# Ports.net
KiCad netlist of a schematic drawn in Altium Designer
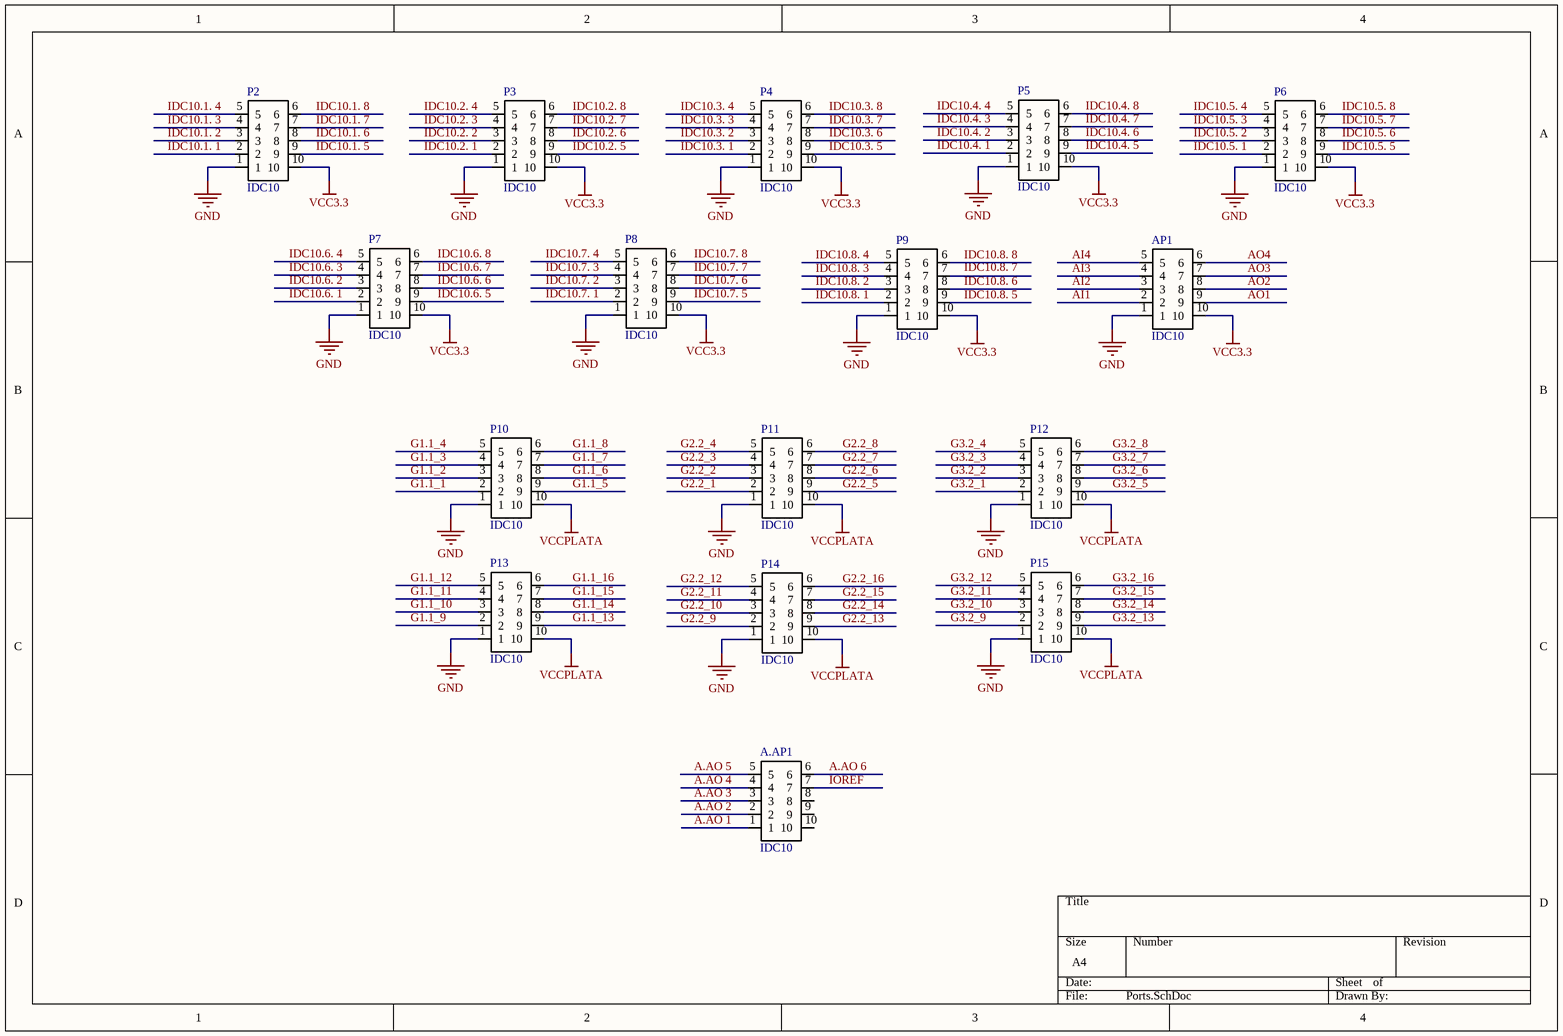
[diagram p0: Ports.SchDoc]

(export (version "E")
  (design (tool "Eeschema 10.0.6"))
  (components
    (comp (ref "A.AP1")
      (value "IDC10")
      (footprint "PcbLib1:IDC10")
      (libsource (lib "Library") (part "IDC10"))
    )
    (comp (ref "AP1") (value "IDC10") (footprint "PcbLib1:IDC10") (libsource (lib "Library") (part "IDC10")))
    (comp (ref "P2") (value "IDC10") (footprint "PcbLib1:IDC10") (libsource (lib "Library") (part "IDC10")))
    (comp (ref "P3") (value "IDC10") (footprint "PcbLib1:IDC10") (libsource (lib "Library") (part "IDC10")))
    (comp (ref "P4") (value "IDC10") (footprint "PcbLib1:IDC10") (libsource (lib "Library") (part "IDC10")))
    (comp (ref "P5") (value "IDC10") (footprint "PcbLib1:IDC10") (libsource (lib "Library") (part "IDC10")))
    (comp (ref "P6") (value "IDC10") (footprint "PcbLib1:IDC10") (libsource (lib "Library") (part "IDC10")))
    (comp (ref "P7") (value "IDC10") (footprint "PcbLib1:IDC10") (libsource (lib "Library") (part "IDC10")))
    (comp (ref "P8") (value "IDC10") (footprint "PcbLib1:IDC10") (libsource (lib "Library") (part "IDC10")))
    (comp (ref "P9") (value "IDC10") (footprint "PcbLib1:IDC10") (libsource (lib "Library") (part "IDC10")))
    (comp (ref "P10") (value "IDC10") (footprint "PcbLib1:IDC10") (libsource (lib "Library") (part "IDC10")))
    (comp (ref "P11") (value "IDC10") (footprint "PcbLib1:IDC10") (libsource (lib "Library") (part "IDC10")))
    (comp (ref "P12") (value "IDC10") (footprint "PcbLib1:IDC10") (libsource (lib "Library") (part "IDC10")))
    (comp (ref "P13") (value "IDC10") (footprint "PcbLib1:IDC10") (libsource (lib "Library") (part "IDC10")))
    (comp (ref "P14") (value "IDC10") (footprint "PcbLib1:IDC10") (libsource (lib "Library") (part "IDC10")))
    (comp (ref "P15") (value "IDC10") (footprint "PcbLib1:IDC10") (libsource (lib "Library") (part "IDC10")))
  )
  (nets
    (net (code "1") (name "/A.AO 1") (class "Default")
      (node (ref "A.AP1") (pin "1") (pinfunction "1_1") (pintype "passive"))
    )
    (net (code "2") (name "/A.AO 2") (class "Default")
      (node (ref "A.AP1") (pin "2") (pinfunction "2_2") (pintype "passive"))
    )
    (net (code "3") (name "/A.AO 3") (class "Default")
      (node (ref "A.AP1") (pin "3") (pinfunction "3_3") (pintype "passive"))
    )
    (net (code "4") (name "/A.AO 4") (class "Default")
      (node (ref "A.AP1") (pin "4") (pinfunction "4_4") (pintype "passive"))
    )
    (net (code "5") (name "/A.AO 5") (class "Default")
      (node (ref "A.AP1") (pin "5") (pinfunction "5_5") (pintype "passive"))
    )
    (net (code "6") (name "/A.AO 6") (class "Default")
      (node (ref "A.AP1") (pin "6") (pinfunction "6_6") (pintype "passive"))
    )
    (net (code "7") (name "/AI1") (class "Default")
      (node (ref "AP1") (pin "2") (pinfunction "2_2") (pintype "passive"))
    )
    (net (code "8") (name "/AI2") (class "Default")
      (node (ref "AP1") (pin "3") (pinfunction "3_3") (pintype "passive"))
    )
    (net (code "9") (name "/AI3") (class "Default")
      (node (ref "AP1") (pin "4") (pinfunction "4_4") (pintype "passive"))
    )
    (net (code "10") (name "/AI4") (class "Default")
      (node (ref "AP1") (pin "5") (pinfunction "5_5") (pintype "passive"))
    )
    (net (code "11") (name "/AO1") (class "Default")
      (node (ref "AP1") (pin "9") (pinfunction "9_9") (pintype "passive"))
    )
    (net (code "12") (name "/AO2") (class "Default")
      (node (ref "AP1") (pin "8") (pinfunction "8_8") (pintype "passive"))
    )
    (net (code "13") (name "/AO3") (class "Default")
      (node (ref "AP1") (pin "7") (pinfunction "7_7") (pintype "passive"))
    )
    (net (code "14") (name "/AO4") (class "Default")
      (node (ref "AP1") (pin "6") (pinfunction "6_6") (pintype "passive"))
    )
    (net (code "15") (name "/G1.1_1") (class "Default")
      (node (ref "P10") (pin "2") (pinfunction "2_2") (pintype "passive"))
    )
    (net (code "16") (name "/G1.1_2") (class "Default")
      (node (ref "P10") (pin "3") (pinfunction "3_3") (pintype "passive"))
    )
    (net (code "17") (name "/G1.1_3") (class "Default")
      (node (ref "P10") (pin "4") (pinfunction "4_4") (pintype "passive"))
    )
    (net (code "18") (name "/G1.1_4") (class "Default")
      (node (ref "P10") (pin "5") (pinfunction "5_5") (pintype "passive"))
    )
    (net (code "19") (name "/G1.1_5") (class "Default")
      (node (ref "P10") (pin "9") (pinfunction "9_9") (pintype "passive"))
    )
    (net (code "20") (name "/G1.1_6") (class "Default")
      (node (ref "P10") (pin "8") (pinfunction "8_8") (pintype "passive"))
    )
    (net (code "21") (name "/G1.1_7") (class "Default")
      (node (ref "P10") (pin "7") (pinfunction "7_7") (pintype "passive"))
    )
    (net (code "22") (name "/G1.1_8") (class "Default")
      (node (ref "P10") (pin "6") (pinfunction "6_6") (pintype "passive"))
    )
    (net (code "23") (name "/G1.1_9") (class "Default")
      (node (ref "P13") (pin "2") (pinfunction "2_2") (pintype "passive"))
    )
    (net (code "24") (name "/G1.1_10") (class "Default")
      (node (ref "P13") (pin "3") (pinfunction "3_3") (pintype "passive"))
    )
    (net (code "25") (name "/G1.1_11") (class "Default")
      (node (ref "P13") (pin "4") (pinfunction "4_4") (pintype "passive"))
    )
    (net (code "26") (name "/G1.1_12") (class "Default")
      (node (ref "P13") (pin "5") (pinfunction "5_5") (pintype "passive"))
    )
    (net (code "27") (name "/G1.1_13") (class "Default")
      (node (ref "P13") (pin "9") (pinfunction "9_9") (pintype "passive"))
    )
    (net (code "28") (name "/G1.1_14") (class "Default")
      (node (ref "P13") (pin "8") (pinfunction "8_8") (pintype "passive"))
    )
    (net (code "29") (name "/G1.1_15") (class "Default")
      (node (ref "P13") (pin "7") (pinfunction "7_7") (pintype "passive"))
    )
    (net (code "30") (name "/G1.1_16") (class "Default")
      (node (ref "P13") (pin "6") (pinfunction "6_6") (pintype "passive"))
    )
    (net (code "31") (name "/G2.2_1") (class "Default")
      (node (ref "P11") (pin "2") (pinfunction "2_2") (pintype "passive"))
    )
    (net (code "32") (name "/G2.2_2") (class "Default")
      (node (ref "P11") (pin "3") (pinfunction "3_3") (pintype "passive"))
    )
    (net (code "33") (name "/G2.2_3") (class "Default")
      (node (ref "P11") (pin "4") (pinfunction "4_4") (pintype "passive"))
    )
    (net (code "34") (name "/G2.2_4") (class "Default")
      (node (ref "P11") (pin "5") (pinfunction "5_5") (pintype "passive"))
    )
    (net (code "35") (name "/G2.2_5") (class "Default")
      (node (ref "P11") (pin "9") (pinfunction "9_9") (pintype "passive"))
    )
    (net (code "36") (name "/G2.2_6") (class "Default")
      (node (ref "P11") (pin "8") (pinfunction "8_8") (pintype "passive"))
    )
    (net (code "37") (name "/G2.2_7") (class "Default")
      (node (ref "P11") (pin "7") (pinfunction "7_7") (pintype "passive"))
    )
    (net (code "38") (name "/G2.2_8") (class "Default")
      (node (ref "P11") (pin "6") (pinfunction "6_6") (pintype "passive"))
    )
    (net (code "39") (name "/G2.2_9") (class "Default")
      (node (ref "P14") (pin "2") (pinfunction "2_2") (pintype "passive"))
    )
    (net (code "40") (name "/G2.2_10") (class "Default")
      (node (ref "P14") (pin "3") (pinfunction "3_3") (pintype "passive"))
    )
    (net (code "41") (name "/G2.2_11") (class "Default")
      (node (ref "P14") (pin "4") (pinfunction "4_4") (pintype "passive"))
    )
    (net (code "42") (name "/G2.2_12") (class "Default")
      (node (ref "P14") (pin "5") (pinfunction "5_5") (pintype "passive"))
    )
    (net (code "43") (name "/G2.2_13") (class "Default")
      (node (ref "P14") (pin "9") (pinfunction "9_9") (pintype "passive"))
    )
    (net (code "44") (name "/G2.2_14") (class "Default")
      (node (ref "P14") (pin "8") (pinfunction "8_8") (pintype "passive"))
    )
    (net (code "45") (name "/G2.2_15") (class "Default")
      (node (ref "P14") (pin "7") (pinfunction "7_7") (pintype "passive"))
    )
    (net (code "46") (name "/G2.2_16") (class "Default")
      (node (ref "P14") (pin "6") (pinfunction "6_6") (pintype "passive"))
    )
    (net (code "47") (name "/G3.2_1") (class "Default")
      (node (ref "P12") (pin "2") (pinfunction "2_2") (pintype "passive"))
    )
    (net (code "48") (name "/G3.2_2") (class "Default")
      (node (ref "P12") (pin "3") (pinfunction "3_3") (pintype "passive"))
    )
    (net (code "49") (name "/G3.2_3") (class "Default")
      (node (ref "P12") (pin "4") (pinfunction "4_4") (pintype "passive"))
    )
    (net (code "50") (name "/G3.2_4") (class "Default")
      (node (ref "P12") (pin "5") (pinfunction "5_5") (pintype "passive"))
    )
    (net (code "51") (name "/G3.2_5") (class "Default")
      (node (ref "P12") (pin "9") (pinfunction "9_9") (pintype "passive"))
    )
    (net (code "52") (name "/G3.2_6") (class "Default")
      (node (ref "P12") (pin "8") (pinfunction "8_8") (pintype "passive"))
    )
    (net (code "53") (name "/G3.2_7") (class "Default")
      (node (ref "P12") (pin "7") (pinfunction "7_7") (pintype "passive"))
    )
    (net (code "54") (name "/G3.2_8") (class "Default")
      (node (ref "P12") (pin "6") (pinfunction "6_6") (pintype "passive"))
    )
    (net (code "55") (name "/G3.2_9") (class "Default")
      (node (ref "P15") (pin "2") (pinfunction "2_2") (pintype "passive"))
    )
    (net (code "56") (name "/G3.2_10") (class "Default")
      (node (ref "P15") (pin "3") (pinfunction "3_3") (pintype "passive"))
    )
    (net (code "57") (name "/G3.2_11") (class "Default")
      (node (ref "P15") (pin "4") (pinfunction "4_4") (pintype "passive"))
    )
    (net (code "58") (name "/G3.2_12") (class "Default")
      (node (ref "P15") (pin "5") (pinfunction "5_5") (pintype "passive"))
    )
    (net (code "59") (name "/G3.2_13") (class "Default")
      (node (ref "P15") (pin "9") (pinfunction "9_9") (pintype "passive"))
    )
    (net (code "60") (name "/G3.2_14") (class "Default")
      (node (ref "P15") (pin "8") (pinfunction "8_8") (pintype "passive"))
    )
    (net (code "61") (name "/G3.2_15") (class "Default")
      (node (ref "P15") (pin "7") (pinfunction "7_7") (pintype "passive"))
    )
    (net (code "62") (name "/G3.2_16") (class "Default")
      (node (ref "P15") (pin "6") (pinfunction "6_6") (pintype "passive"))
    )
    (net (code "63") (name "/IDC10.1. 1") (class "Default")
      (node (ref "P2") (pin "2") (pinfunction "2_2") (pintype "passive"))
    )
    (net (code "64") (name "/IDC10.1. 2") (class "Default")
      (node (ref "P2") (pin "3") (pinfunction "3_3") (pintype "passive"))
    )
    (net (code "65") (name "/IDC10.1. 3") (class "Default")
      (node (ref "P2") (pin "4") (pinfunction "4_4") (pintype "passive"))
    )
    (net (code "66") (name "/IDC10.1. 4") (class "Default")
      (node (ref "P2") (pin "5") (pinfunction "5_5") (pintype "passive"))
    )
    (net (code "67") (name "/IDC10.1. 5") (class "Default")
      (node (ref "P2") (pin "9") (pinfunction "9_9") (pintype "passive"))
    )
    (net (code "68") (name "/IDC10.1. 6") (class "Default")
      (node (ref "P2") (pin "8") (pinfunction "8_8") (pintype "passive"))
    )
    (net (code "69") (name "/IDC10.1. 7") (class "Default")
      (node (ref "P2") (pin "7") (pinfunction "7_7") (pintype "passive"))
    )
    (net (code "70") (name "/IDC10.1. 8") (class "Default")
      (node (ref "P2") (pin "6") (pinfunction "6_6") (pintype "passive"))
    )
    (net (code "71") (name "/IDC10.2. 1") (class "Default")
      (node (ref "P3") (pin "2") (pinfunction "2_2") (pintype "passive"))
    )
    (net (code "72") (name "/IDC10.2. 2") (class "Default")
      (node (ref "P3") (pin "3") (pinfunction "3_3") (pintype "passive"))
    )
    (net (code "73") (name "/IDC10.2. 3") (class "Default")
      (node (ref "P3") (pin "4") (pinfunction "4_4") (pintype "passive"))
    )
    (net (code "74") (name "/IDC10.2. 4") (class "Default")
      (node (ref "P3") (pin "5") (pinfunction "5_5") (pintype "passive"))
    )
    (net (code "75") (name "/IDC10.2. 5") (class "Default")
      (node (ref "P3") (pin "9") (pinfunction "9_9") (pintype "passive"))
    )
    (net (code "76") (name "/IDC10.2. 6") (class "Default")
      (node (ref "P3") (pin "8") (pinfunction "8_8") (pintype "passive"))
    )
    (net (code "77") (name "/IDC10.2. 7") (class "Default")
      (node (ref "P3") (pin "7") (pinfunction "7_7") (pintype "passive"))
    )
    (net (code "78") (name "/IDC10.2. 8") (class "Default")
      (node (ref "P3") (pin "6") (pinfunction "6_6") (pintype "passive"))
    )
    (net (code "79") (name "/IDC10.3. 1") (class "Default")
      (node (ref "P4") (pin "2") (pinfunction "2_2") (pintype "passive"))
    )
    (net (code "80") (name "/IDC10.3. 2") (class "Default")
      (node (ref "P4") (pin "3") (pinfunction "3_3") (pintype "passive"))
    )
    (net (code "81") (name "/IDC10.3. 3") (class "Default")
      (node (ref "P4") (pin "4") (pinfunction "4_4") (pintype "passive"))
    )
    (net (code "82") (name "/IDC10.3. 4") (class "Default")
      (node (ref "P4") (pin "5") (pinfunction "5_5") (pintype "passive"))
    )
    (net (code "83") (name "/IDC10.3. 5") (class "Default")
      (node (ref "P4") (pin "9") (pinfunction "9_9") (pintype "passive"))
    )
    (net (code "84") (name "/IDC10.3. 6") (class "Default")
      (node (ref "P4") (pin "8") (pinfunction "8_8") (pintype "passive"))
    )
    (net (code "85") (name "/IDC10.3. 7") (class "Default")
      (node (ref "P4") (pin "7") (pinfunction "7_7") (pintype "passive"))
    )
    (net (code "86") (name "/IDC10.3. 8") (class "Default")
      (node (ref "P4") (pin "6") (pinfunction "6_6") (pintype "passive"))
    )
    (net (code "87") (name "/IDC10.4. 1") (class "Default")
      (node (ref "P5") (pin "2") (pinfunction "2_2") (pintype "passive"))
    )
    (net (code "88") (name "/IDC10.4. 2") (class "Default")
      (node (ref "P5") (pin "3") (pinfunction "3_3") (pintype "passive"))
    )
    (net (code "89") (name "/IDC10.4. 3") (class "Default")
      (node (ref "P5") (pin "4") (pinfunction "4_4") (pintype "passive"))
    )
    (net (code "90") (name "/IDC10.4. 4") (class "Default")
      (node (ref "P5") (pin "5") (pinfunction "5_5") (pintype "passive"))
    )
    (net (code "91") (name "/IDC10.4. 5") (class "Default")
      (node (ref "P5") (pin "9") (pinfunction "9_9") (pintype "passive"))
    )
    (net (code "92") (name "/IDC10.4. 6") (class "Default")
      (node (ref "P5") (pin "8") (pinfunction "8_8") (pintype "passive"))
    )
    (net (code "93") (name "/IDC10.4. 7") (class "Default")
      (node (ref "P5") (pin "7") (pinfunction "7_7") (pintype "passive"))
    )
    (net (code "94") (name "/IDC10.4. 8") (class "Default")
      (node (ref "P5") (pin "6") (pinfunction "6_6") (pintype "passive"))
    )
    (net (code "95") (name "/IDC10.5. 1") (class "Default")
      (node (ref "P6") (pin "2") (pinfunction "2_2") (pintype "passive"))
    )
    (net (code "96") (name "/IDC10.5. 2") (class "Default")
      (node (ref "P6") (pin "3") (pinfunction "3_3") (pintype "passive"))
    )
    (net (code "97") (name "/IDC10.5. 3") (class "Default")
      (node (ref "P6") (pin "4") (pinfunction "4_4") (pintype "passive"))
    )
    (net (code "98") (name "/IDC10.5. 4") (class "Default")
      (node (ref "P6") (pin "5") (pinfunction "5_5") (pintype "passive"))
    )
    (net (code "99") (name "/IDC10.5. 5") (class "Default")
      (node (ref "P6") (pin "9") (pinfunction "9_9") (pintype "passive"))
    )
    (net (code "100") (name "/IDC10.5. 6") (class "Default")
      (node (ref "P6") (pin "8") (pinfunction "8_8") (pintype "passive"))
    )
    (net (code "101") (name "/IDC10.5. 7") (class "Default")
      (node (ref "P6") (pin "7") (pinfunction "7_7") (pintype "passive"))
    )
    (net (code "102") (name "/IDC10.5. 8") (class "Default")
      (node (ref "P6") (pin "6") (pinfunction "6_6") (pintype "passive"))
    )
    (net (code "103") (name "/IDC10.6. 1") (class "Default")
      (node (ref "P7") (pin "2") (pinfunction "2_2") (pintype "passive"))
    )
    (net (code "104") (name "/IDC10.6. 2") (class "Default")
      (node (ref "P7") (pin "3") (pinfunction "3_3") (pintype "passive"))
    )
    (net (code "105") (name "/IDC10.6. 3") (class "Default")
      (node (ref "P7") (pin "4") (pinfunction "4_4") (pintype "passive"))
    )
    (net (code "106") (name "/IDC10.6. 4") (class "Default")
      (node (ref "P7") (pin "5") (pinfunction "5_5") (pintype "passive"))
    )
    (net (code "107") (name "/IDC10.6. 5") (class "Default")
      (node (ref "P7") (pin "9") (pinfunction "9_9") (pintype "passive"))
    )
    (net (code "108") (name "/IDC10.6. 6") (class "Default")
      (node (ref "P7") (pin "8") (pinfunction "8_8") (pintype "passive"))
    )
    (net (code "109") (name "/IDC10.6. 7") (class "Default")
      (node (ref "P7") (pin "7") (pinfunction "7_7") (pintype "passive"))
    )
    (net (code "110") (name "/IDC10.6. 8") (class "Default")
      (node (ref "P7") (pin "6") (pinfunction "6_6") (pintype "passive"))
    )
    (net (code "111") (name "/IDC10.7. 1") (class "Default")
      (node (ref "P8") (pin "2") (pinfunction "2_2") (pintype "passive"))
    )
    (net (code "112") (name "/IDC10.7. 2") (class "Default")
      (node (ref "P8") (pin "3") (pinfunction "3_3") (pintype "passive"))
    )
    (net (code "113") (name "/IDC10.7. 3") (class "Default")
      (node (ref "P8") (pin "4") (pinfunction "4_4") (pintype "passive"))
    )
    (net (code "114") (name "/IDC10.7. 4") (class "Default")
      (node (ref "P8") (pin "5") (pinfunction "5_5") (pintype "passive"))
    )
    (net (code "115") (name "/IDC10.7. 5") (class "Default")
      (node (ref "P8") (pin "9") (pinfunction "9_9") (pintype "passive"))
    )
    (net (code "116") (name "/IDC10.7. 6") (class "Default")
      (node (ref "P8") (pin "8") (pinfunction "8_8") (pintype "passive"))
    )
    (net (code "117") (name "/IDC10.7. 7") (class "Default")
      (node (ref "P8") (pin "7") (pinfunction "7_7") (pintype "passive"))
    )
    (net (code "118") (name "/IDC10.7. 8") (class "Default")
      (node (ref "P8") (pin "6") (pinfunction "6_6") (pintype "passive"))
    )
    (net (code "119") (name "/IDC10.8. 1") (class "Default")
      (node (ref "P9") (pin "2") (pinfunction "2_2") (pintype "passive"))
    )
    (net (code "120") (name "/IDC10.8. 2") (class "Default")
      (node (ref "P9") (pin "3") (pinfunction "3_3") (pintype "passive"))
    )
    (net (code "121") (name "/IDC10.8. 3") (class "Default")
      (node (ref "P9") (pin "4") (pinfunction "4_4") (pintype "passive"))
    )
    (net (code "122") (name "/IDC10.8. 4") (class "Default")
      (node (ref "P9") (pin "5") (pinfunction "5_5") (pintype "passive"))
    )
    (net (code "123") (name "/IDC10.8. 5") (class "Default")
      (node (ref "P9") (pin "9") (pinfunction "9_9") (pintype "passive"))
    )
    (net (code "124") (name "/IDC10.8. 6") (class "Default")
      (node (ref "P9") (pin "8") (pinfunction "8_8") (pintype "passive"))
    )
    (net (code "126") (name "/IDC10.8. 8") (class "Default")
      (node (ref "P9") (pin "6") (pinfunction "6_6") (pintype "passive"))
    )
    (net (code "127") (name "/IOREF") (class "Default")
      (node (ref "A.AP1") (pin "7") (pinfunction "7_7") (pintype "passive"))
    )
    (net (code "128") (name "GND") (class "Default")
      (node (ref "AP1") (pin "1") (pinfunction "1_1") (pintype "passive"))
      (node (ref "P10") (pin "1") (pinfunction "1_1") (pintype "passive"))
      (node (ref "P11") (pin "1") (pinfunction "1_1") (pintype "passive"))
      (node (ref "P12") (pin "1") (pinfunction "1_1") (pintype "passive"))
      (node (ref "P13") (pin "1") (pinfunction "1_1") (pintype "passive"))
      (node (ref "P14") (pin "1") (pinfunction "1_1") (pintype "passive"))
      (node (ref "P15") (pin "1") (pinfunction "1_1") (pintype "passive"))
      (node (ref "P2") (pin "1") (pinfunction "1_1") (pintype "passive"))
      (node (ref "P3") (pin "1") (pinfunction "1_1") (pintype "passive"))
      (node (ref "P4") (pin "1") (pinfunction "1_1") (pintype "passive"))
      (node (ref "P5") (pin "1") (pinfunction "1_1") (pintype "passive"))
      (node (ref "P6") (pin "1") (pinfunction "1_1") (pintype "passive"))
      (node (ref "P7") (pin "1") (pinfunction "1_1") (pintype "passive"))
      (node (ref "P8") (pin "1") (pinfunction "1_1") (pintype "passive"))
      (node (ref "P9") (pin "1") (pinfunction "1_1") (pintype "passive"))
    )
    (net (code "129") (name "VCC3.3") (class "Default")
      (node (ref "AP1") (pin "10") (pinfunction "10_10") (pintype "passive"))
      (node (ref "P2") (pin "10") (pinfunction "10_10") (pintype "passive"))
      (node (ref "P3") (pin "10") (pinfunction "10_10") (pintype "passive"))
      (node (ref "P4") (pin "10") (pinfunction "10_10") (pintype "passive"))
      (node (ref "P5") (pin "10") (pinfunction "10_10") (pintype "passive"))
      (node (ref "P6") (pin "10") (pinfunction "10_10") (pintype "passive"))
      (node (ref "P7") (pin "10") (pinfunction "10_10") (pintype "passive"))
      (node (ref "P8") (pin "10") (pinfunction "10_10") (pintype "passive"))
      (node (ref "P9") (pin "10") (pinfunction "10_10") (pintype "passive"))
    )
    (net (code "130") (name "VCCPLATA") (class "Default")
      (node (ref "P10") (pin "10") (pinfunction "10_10") (pintype "passive"))
      (node (ref "P11") (pin "10") (pinfunction "10_10") (pintype "passive"))
      (node (ref "P12") (pin "10") (pinfunction "10_10") (pintype "passive"))
      (node (ref "P13") (pin "10") (pinfunction "10_10") (pintype "passive"))
      (node (ref "P14") (pin "10") (pinfunction "10_10") (pintype "passive"))
      (node (ref "P15") (pin "10") (pinfunction "10_10") (pintype "passive"))
    )
    (net (code "131") (name "unconnected-(A.AP1-Pad8)") (class "Default")
      (node (ref "A.AP1") (pin "8") (pinfunction "8_8") (pintype "passive"))
    )
    (net (code "132") (name "unconnected-(A.AP1-Pad9)") (class "Default")
      (node (ref "A.AP1") (pin "9") (pinfunction "9_9") (pintype "passive"))
    )
    (net (code "133") (name "unconnected-(A.AP1-Pad10)") (class "Default")
      (node (ref "A.AP1") (pin "10") (pinfunction "10_10") (pintype "passive"))
    )
    (net (code "134") (name "unconnected-(P9-Pad7)") (class "Default")
      (node (ref "P9") (pin "7") (pinfunction "7_7") (pintype "passive"))
    )
  )
)
